# interface_eagle_1.net
KiCad netlist of a schematic drawn in Altium Designer
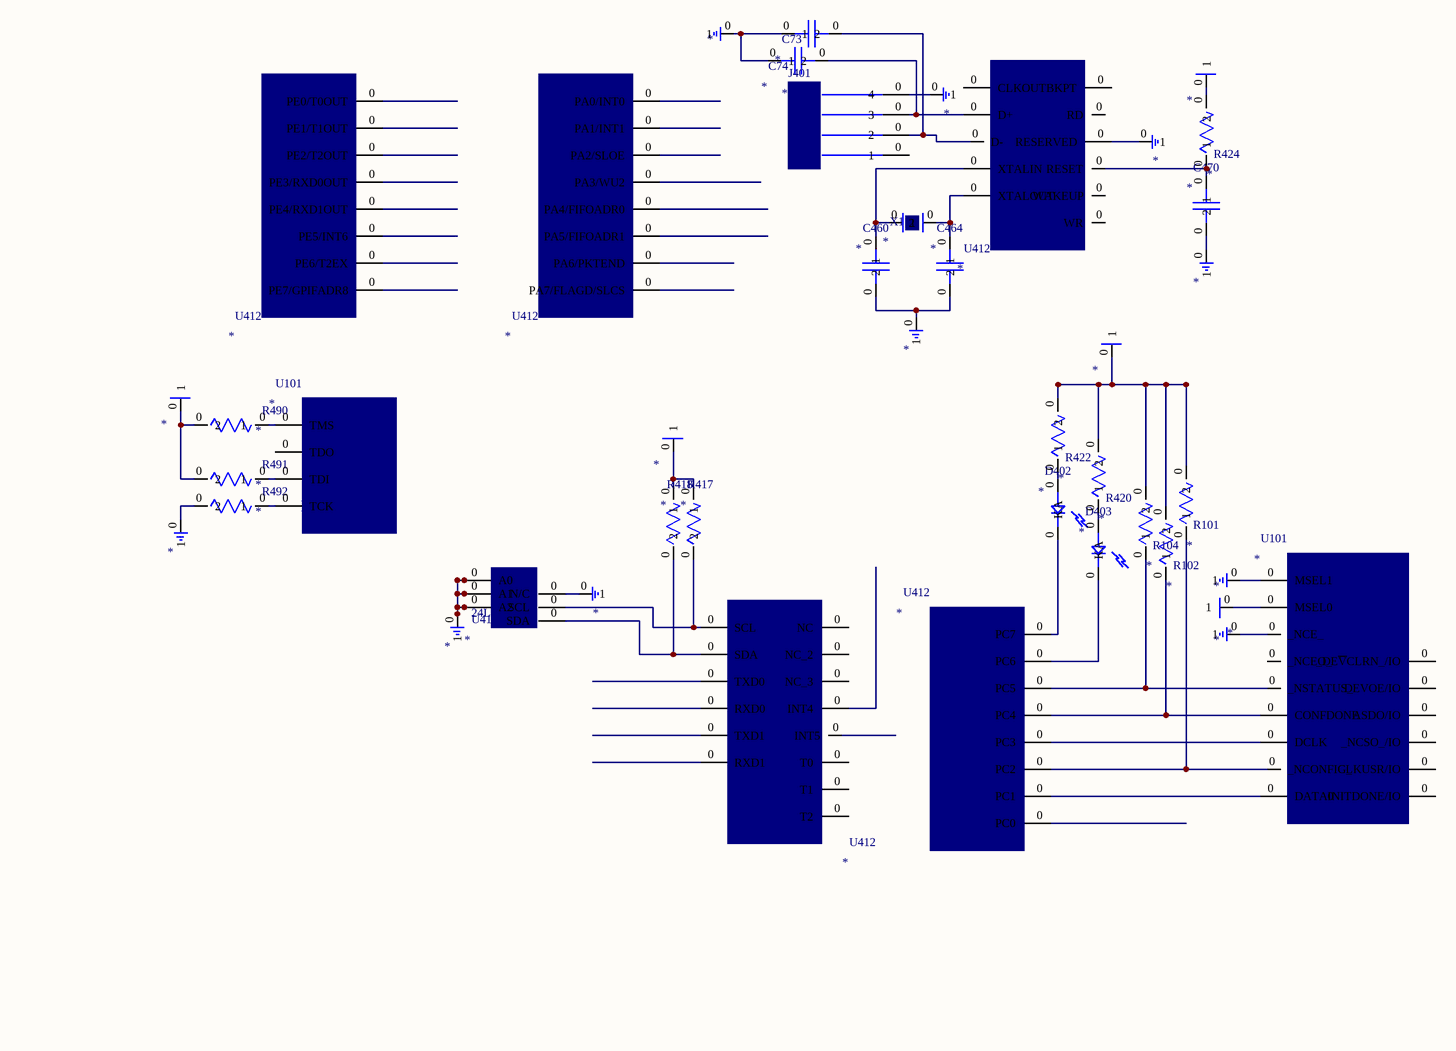
[diagram p0: interface_eagle_1.SchDoc]

(export (version "E")
  (design (tool "Eeschema 10.0.6"))
  (components
    (comp (ref "C73") (value "*") (libsource (lib "") (part "CAPACITOR-1_3")))
    (comp (ref "C74") (value "*") (libsource (lib "") (part "CAPACITOR-1_4")))
    (comp (ref "C460") (value "*") (libsource (lib "") (part "CAPACITOR-1_1")))
    (comp (ref "C464") (value "*") (libsource (lib "") (part "CAPACITOR-1_2")))
    (comp (ref "C470") (value "*") (libsource (lib "openjson") (part "CAPACITOR-1")))
    (comp (ref "D402") (value "*") (libsource (lib "openjson") (part "LED-1")))
    (comp (ref "D403") (value "*") (libsource (lib "") (part "LED-1_1")))
    (comp (ref "GENERIC-POWER") (value "*") (libsource (lib "openjson") (part "GENERIC-POWER")))
    (comp (ref "GENERIC-POWER-4") (value "*") (libsource (lib "openjson") (part "GENERIC-POWER")))
    (comp (ref "GENERIC-POWER-9") (value "*") (libsource (lib "openjson") (part "GENERIC-POWER")))
    (comp (ref "GENERIC-POWER-10") (value "*") (libsource (lib "openjson") (part "GENERIC-POWER")))
    (comp (ref "GENERIC-POWER-14") (value "*") (libsource (lib "openjson") (part "GENERIC-POWER")))
    (comp (ref "GND-1") (value "*") (libsource (lib "openjson") (part "GND-1")))
    (comp (ref "GND-1-3") (value "*") (libsource (lib "openjson") (part "GND-1")))
    (comp (ref "GND-1-5") (value "*") (libsource (lib "") (part "GND-1_1")))
    (comp (ref "GND-1-6") (value "*") (libsource (lib "") (part "GND-1_2")))
    (comp (ref "GND-1-7") (value "*") (libsource (lib "") (part "GND-1_1")))
    (comp (ref "GND-1-8") (value "*") (libsource (lib "") (part "GND-1_2")))
    (comp (ref "GND-1-11") (value "*") (libsource (lib "") (part "GND-1_2")))
    (comp (ref "GND-1-12") (value "*") (libsource (lib "") (part "GND-1_1")))
    (comp (ref "GND-1-13") (value "*") (libsource (lib "") (part "GND-1_2")))
    (comp (ref "GND-1-17") (value "*") (libsource (lib "openjson") (part "GND-1")))
    (comp (ref "J401") (value "*") (libsource (lib "openjson") (part "CONNECTOR4-1_MIRRORED")))
    (comp (ref "R101") (value "*") (libsource (lib "") (part "RESISTOR-1_10")))
    (comp (ref "R102") (value "*") (libsource (lib "") (part "RESISTOR-1_9")))
    (comp (ref "R104") (value "*") (libsource (lib "") (part "RESISTOR-1_1")))
    (comp (ref "R417") (value "*") (libsource (lib "") (part "RESISTOR-1_8")))
    (comp (ref "R418") (value "*") (libsource (lib "") (part "RESISTOR-1_5")))
    (comp (ref "R420") (value "*") (libsource (lib "") (part "RESISTOR-1_3")))
    (comp (ref "R422") (value "*") (libsource (lib "openjson") (part "RESISTOR-1")))
    (comp (ref "R424") (value "*") (libsource (lib "") (part "RESISTOR-1_2")))
    (comp (ref "R490") (value "*") (libsource (lib "") (part "RESISTOR-1_4")))
    (comp (ref "R491") (value "*") (libsource (lib "") (part "RESISTOR-1_7")))
    (comp (ref "R492") (value "*") (libsource (lib "") (part "RESISTOR-1_6")))
    (comp (ref "U101") (value "*") (libsource (lib "openjson") (part "EP1C12-PQ240-CFG_MIRRORED")))
    (comp (ref "U101-2") (value "*") (libsource (lib "openjson") (part "EP1C12-PQ240-JTAG_MIRRORED")))
    (comp (ref "U412") (value "*") (libsource (lib "openjson") (part "CY7C68013-TQ100-CTRL")))
    (comp (ref "U412-0") (value "*") (libsource (lib "openjson") (part "CY7C68013-TQ100-MISC_MIRRORED")))
    (comp (ref "U412-1") (value "*") (libsource (lib "openjson") (part "CY7C68013-TQ100-PC_MIRRORED")))
    (comp (ref "U412-15") (value "*") (libsource (lib "openjson") (part "CY7C68013-TQ100-PA")))
    (comp (ref "U412-16") (value "*") (libsource (lib "openjson") (part "CY7C68013-TQ100-PE")))
    (comp (ref "U413") (value "*") (libsource (lib "openjson") (part "24CXX-1")))
    (comp (ref "X1") (value "*") (libsource (lib "openjson") (part "CRYSTAL-1")))
  )
  (nets
    (net (code "1") (name "Net-(C73-1)") (class "Default")
      (node (ref "C73") (pin "0") (pinfunction "1_0") (pintype "passive"))
      (node (ref "C74") (pin "0") (pinfunction "1_0") (pintype "passive"))
      (node (ref "GND-1-17") (pin "0") (pinfunction "1_0") (pintype "passive"))
    )
    (net (code "2") (name "Net-(C73-2)") (class "Default")
      (node (ref "C73") (pin "0") (pinfunction "2_0") (pintype "passive"))
      (node (ref "J401") (pin "0") (pinfunction "2_0") (pintype "passive"))
      (node (ref "U412") (pin "0") (pinfunction "D-_0") (pintype "passive"))
    )
    (net (code "3") (name "Net-(C74-2)") (class "Default")
      (node (ref "C74") (pin "0") (pinfunction "2_0") (pintype "passive"))
      (node (ref "J401") (pin "0") (pinfunction "3_0") (pintype "passive"))
      (node (ref "U412") (pin "0") (pinfunction "D+_0") (pintype "passive"))
    )
    (net (code "4") (name "Net-(C460-1)") (class "Default")
      (node (ref "C460") (pin "0") (pinfunction "1_0") (pintype "passive"))
      (node (ref "U412") (pin "0") (pinfunction "XTALIN_0") (pintype "passive"))
      (node (ref "X1") (pin "0") (pinfunction "1_0") (pintype "passive"))
    )
    (net (code "5") (name "Net-(C460-2)") (class "Default")
      (node (ref "C460") (pin "0") (pinfunction "2_0") (pintype "passive"))
      (node (ref "C464") (pin "0") (pinfunction "2_0") (pintype "passive"))
      (node (ref "GND-1-6") (pin "0") (pinfunction "1_0") (pintype "passive"))
    )
    (net (code "6") (name "Net-(C464-1)") (class "Default")
      (node (ref "C464") (pin "0") (pinfunction "1_0") (pintype "passive"))
      (node (ref "U412") (pin "0") (pinfunction "XTALOUT_0") (pintype "passive"))
      (node (ref "X1") (pin "0") (pinfunction "2_0") (pintype "passive"))
    )
    (net (code "7") (name "Net-(C470-1)") (class "Default")
      (node (ref "C470") (pin "0") (pinfunction "1_0") (pintype "passive"))
      (node (ref "R424") (pin "0") (pinfunction "1_0") (pintype "passive"))
      (node (ref "U412") (pin "0") (pinfunction "RESET_0") (pintype "passive"))
    )
    (net (code "8") (name "Net-(C470-2)") (class "Default")
      (node (ref "C470") (pin "0") (pinfunction "2_0") (pintype "passive"))
      (node (ref "GND-1-8") (pin "0") (pinfunction "1_0") (pintype "passive"))
    )
    (net (code "9") (name "Net-(D402-A)") (class "Default")
      (node (ref "D402") (pin "0") (pinfunction "A_0") (pintype "passive"))
      (node (ref "R422") (pin "0") (pinfunction "1_0") (pintype "passive"))
    )
    (net (code "10") (name "Net-(D402-K)") (class "Default")
      (node (ref "D402") (pin "0") (pinfunction "K_0") (pintype "passive"))
      (node (ref "U412-1") (pin "0") (pinfunction "PC7_0") (pintype "passive"))
    )
    (net (code "11") (name "Net-(D403-A)") (class "Default")
      (node (ref "D403") (pin "0") (pinfunction "A_0") (pintype "passive"))
      (node (ref "R420") (pin "0") (pinfunction "1_0") (pintype "passive"))
    )
    (net (code "12") (name "Net-(D403-K)") (class "Default")
      (node (ref "D403") (pin "0") (pinfunction "K_0") (pintype "passive"))
      (node (ref "U412-1") (pin "0") (pinfunction "PC6_0") (pintype "passive"))
    )
    (net (code "13") (name "Net-(GENERIC-POWER-1)") (class "Default")
      (node (ref "GENERIC-POWER") (pin "0") (pinfunction "1_0") (pintype "passive"))
      (node (ref "U101") (pin "0") (pinfunction "MSEL0_0") (pintype "passive"))
    )
    (net (code "14") (name "Net-(GENERIC-POWER-4-1)") (class "Default")
      (node (ref "GENERIC-POWER-4") (pin "0") (pinfunction "1_0") (pintype "passive"))
      (node (ref "R101") (pin "0") (pinfunction "2_0") (pintype "passive"))
      (node (ref "R102") (pin "0") (pinfunction "2_0") (pintype "passive"))
      (node (ref "R104") (pin "0") (pinfunction "2_0") (pintype "passive"))
      (node (ref "R420") (pin "0") (pinfunction "2_0") (pintype "passive"))
      (node (ref "R422") (pin "0") (pinfunction "2_0") (pintype "passive"))
    )
    (net (code "15") (name "Net-(GENERIC-POWER-9-1)") (class "Default")
      (node (ref "GENERIC-POWER-9") (pin "0") (pinfunction "1_0") (pintype "passive"))
      (node (ref "R424") (pin "0") (pinfunction "2_0") (pintype "passive"))
    )
    (net (code "16") (name "Net-(GENERIC-POWER-10-1)") (class "Default")
      (node (ref "GENERIC-POWER-10") (pin "0") (pinfunction "1_0") (pintype "passive"))
      (node (ref "R490") (pin "0") (pinfunction "2_0") (pintype "passive"))
      (node (ref "R491") (pin "0") (pinfunction "2_0") (pintype "passive"))
    )
    (net (code "17") (name "Net-(GENERIC-POWER-14-1)") (class "Default")
      (node (ref "GENERIC-POWER-14") (pin "0") (pinfunction "1_0") (pintype "passive"))
      (node (ref "R417") (pin "0") (pinfunction "1_0") (pintype "passive"))
      (node (ref "R418") (pin "0") (pinfunction "1_0") (pintype "passive"))
    )
    (net (code "18") (name "Net-(GND-1-1)") (class "Default")
      (node (ref "GND-1") (pin "0") (pinfunction "1_0") (pintype "passive"))
      (node (ref "U101") (pin "0") (pinfunction "_NCE__0") (pintype "passive"))
    )
    (net (code "19") (name "Net-(GND-1-3-1)") (class "Default")
      (node (ref "GND-1-3") (pin "0") (pinfunction "1_0") (pintype "passive"))
      (node (ref "U101") (pin "0") (pinfunction "MSEL1_0") (pintype "passive"))
    )
    (net (code "20") (name "Net-(GND-1-5-1)") (class "Default")
      (node (ref "GND-1-5") (pin "0") (pinfunction "1_0") (pintype "passive"))
      (node (ref "J401") (pin "0") (pinfunction "4_0") (pintype "passive"))
    )
    (net (code "21") (name "Net-(GND-1-7-1)") (class "Default")
      (node (ref "GND-1-7") (pin "0") (pinfunction "1_0") (pintype "passive"))
      (node (ref "U412") (pin "0") (pinfunction "RESERVED_0") (pintype "passive"))
    )
    (net (code "22") (name "Net-(GND-1-11-1)") (class "Default")
      (node (ref "GND-1-11") (pin "0") (pinfunction "1_0") (pintype "passive"))
      (node (ref "R492") (pin "0") (pinfunction "2_0") (pintype "passive"))
    )
    (net (code "23") (name "Net-(GND-1-12-1)") (class "Default")
      (node (ref "GND-1-12") (pin "0") (pinfunction "1_0") (pintype "passive"))
      (node (ref "U413") (pin "0") (pinfunction "N/C_0") (pintype "passive"))
    )
    (net (code "24") (name "Net-(GND-1-13-1)") (class "Default")
      (node (ref "GND-1-13") (pin "0") (pinfunction "1_0") (pintype "passive"))
      (node (ref "U413") (pin "0") (pinfunction "A0_0") (pintype "passive"))
    )
    (net (code "25") (name "Net-(R101-1)") (class "Default")
      (node (ref "R101") (pin "0") (pinfunction "1_0") (pintype "passive"))
      (node (ref "U101") (pin "0") (pinfunction "_NCONFIG__0") (pintype "passive"))
      (node (ref "U412-1") (pin "0") (pinfunction "PC2_0") (pintype "passive"))
    )
    (net (code "26") (name "Net-(R102-1)") (class "Default")
      (node (ref "R102") (pin "0") (pinfunction "1_0") (pintype "passive"))
      (node (ref "U101") (pin "0") (pinfunction "CONFDONE_0") (pintype "passive"))
      (node (ref "U412-1") (pin "0") (pinfunction "PC4_0") (pintype "passive"))
    )
    (net (code "27") (name "Net-(R104-1)") (class "Default")
      (node (ref "R104") (pin "0") (pinfunction "1_0") (pintype "passive"))
      (node (ref "U101") (pin "0") (pinfunction "_NSTATUS__0") (pintype "passive"))
      (node (ref "U412-1") (pin "0") (pinfunction "PC5_0") (pintype "passive"))
    )
    (net (code "28") (name "Net-(R417-2)") (class "Default")
      (node (ref "R417") (pin "0") (pinfunction "2_0") (pintype "passive"))
      (node (ref "U412-0") (pin "0") (pinfunction "SCL_0") (pintype "passive"))
      (node (ref "U413") (pin "0") (pinfunction "SCL_0") (pintype "passive"))
    )
    (net (code "29") (name "Net-(R418-2)") (class "Default")
      (node (ref "R418") (pin "0") (pinfunction "2_0") (pintype "passive"))
      (node (ref "U412-0") (pin "0") (pinfunction "SDA_0") (pintype "passive"))
      (node (ref "U413") (pin "0") (pinfunction "SDA_0") (pintype "passive"))
    )
    (net (code "30") (name "Net-(R490-1)") (class "Default")
      (node (ref "R490") (pin "0") (pinfunction "1_0") (pintype "passive"))
      (node (ref "U101-2") (pin "0") (pinfunction "TMS_0") (pintype "passive"))
    )
    (net (code "31") (name "Net-(R491-1)") (class "Default")
      (node (ref "R491") (pin "0") (pinfunction "1_0") (pintype "passive"))
      (node (ref "U101-2") (pin "0") (pinfunction "TDI_0") (pintype "passive"))
    )
    (net (code "32") (name "Net-(R492-1)") (class "Default")
      (node (ref "R492") (pin "0") (pinfunction "1_0") (pintype "passive"))
      (node (ref "U101-2") (pin "0") (pinfunction "TCK_0") (pintype "passive"))
    )
    (net (code "33") (name "Net-(U101-DATA0)") (class "Default")
      (node (ref "U101") (pin "0") (pinfunction "DATA0_0") (pintype "passive"))
      (node (ref "U412-1") (pin "0") (pinfunction "PC1_0") (pintype "passive"))
    )
    (net (code "34") (name "Net-(U101-DCLK)") (class "Default")
      (node (ref "U101") (pin "0") (pinfunction "DCLK_0") (pintype "passive"))
      (node (ref "U412-1") (pin "0") (pinfunction "PC3_0") (pintype "passive"))
    )
    (net (code "35") (name "unconnected-(J401-1-Pad0)") (class "Default")
      (node (ref "J401") (pin "0") (pinfunction "1_0") (pintype "passive"))
    )
    (net (code "36") (name "unconnected-(U101-2-TDO-Pad0)") (class "Default")
      (node (ref "U101-2") (pin "0") (pinfunction "TDO_0") (pintype "passive"))
    )
    (net (code "37") (name "unconnected-(U101-ASDO{slash}IO-Pad0)") (class "Default")
      (node (ref "U101") (pin "0") (pinfunction "ASDO/IO_0") (pintype "passive"))
    )
    (net (code "38") (name "unconnected-(U101-CLKUSR{slash}IO-Pad0)") (class "Default")
      (node (ref "U101") (pin "0") (pinfunction "CLKUSR/IO_0") (pintype "passive"))
    )
    (net (code "39") (name "unconnected-(U101-DEVOE{slash}IO-Pad0)") (class "Default")
      (node (ref "U101") (pin "0") (pinfunction "DEVOE/IO_0") (pintype "passive"))
    )
    (net (code "40") (name "unconnected-(U101-INITDONE{slash}IO-Pad0)") (class "Default")
      (node (ref "U101") (pin "0") (pinfunction "INITDONE/IO_0") (pintype "passive"))
    )
    (net (code "41") (name "unconnected-(U101-_DE~{V}CLRN_{slash}IO-Pad0)") (class "Default")
      (node (ref "U101") (pin "0") (pinfunction "_DE~{V}CLRN_/IO_0") (pintype "passive"))
    )
    (net (code "42") (name "unconnected-(U101-_NCEO_-Pad0)") (class "Default")
      (node (ref "U101") (pin "0") (pinfunction "_NCEO__0") (pintype "passive"))
    )
    (net (code "43") (name "unconnected-(U101-_NCSO_{slash}IO-Pad0)") (class "Default")
      (node (ref "U101") (pin "0") (pinfunction "_NCSO_/IO_0") (pintype "passive"))
    )
    (net (code "44") (name "unconnected-(U412-0-INT4-Pad0)") (class "Default")
      (node (ref "U412-0") (pin "0") (pinfunction "INT4_0") (pintype "passive"))
    )
    (net (code "45") (name "unconnected-(U412-0-INT5-Pad0)") (class "Default")
      (node (ref "U412-0") (pin "0") (pinfunction "INT5_0") (pintype "passive"))
    )
    (net (code "46") (name "unconnected-(U412-0-NC-Pad0)") (class "Default")
      (node (ref "U412-0") (pin "0") (pinfunction "NC_0") (pintype "passive"))
    )
    (net (code "47") (name "unconnected-(U412-0-NC_2-Pad0)") (class "Default")
      (node (ref "U412-0") (pin "0") (pinfunction "NC_2_0") (pintype "passive"))
    )
    (net (code "48") (name "unconnected-(U412-0-NC_3-Pad0)") (class "Default")
      (node (ref "U412-0") (pin "0") (pinfunction "NC_3_0") (pintype "passive"))
    )
    (net (code "49") (name "unconnected-(U412-0-RXD0-Pad0)") (class "Default")
      (node (ref "U412-0") (pin "0") (pinfunction "RXD0_0") (pintype "passive"))
    )
    (net (code "50") (name "unconnected-(U412-0-RXD1-Pad0)") (class "Default")
      (node (ref "U412-0") (pin "0") (pinfunction "RXD1_0") (pintype "passive"))
    )
    (net (code "51") (name "unconnected-(U412-0-T0-Pad0)") (class "Default")
      (node (ref "U412-0") (pin "0") (pinfunction "T0_0") (pintype "passive"))
    )
    (net (code "52") (name "unconnected-(U412-0-T1-Pad0)") (class "Default")
      (node (ref "U412-0") (pin "0") (pinfunction "T1_0") (pintype "passive"))
    )
    (net (code "53") (name "unconnected-(U412-0-T2-Pad0)") (class "Default")
      (node (ref "U412-0") (pin "0") (pinfunction "T2_0") (pintype "passive"))
    )
    (net (code "54") (name "unconnected-(U412-0-TXD0-Pad0)") (class "Default")
      (node (ref "U412-0") (pin "0") (pinfunction "TXD0_0") (pintype "passive"))
    )
    (net (code "55") (name "unconnected-(U412-0-TXD1-Pad0)") (class "Default")
      (node (ref "U412-0") (pin "0") (pinfunction "TXD1_0") (pintype "passive"))
    )
    (net (code "56") (name "unconnected-(U412-1-PC0-Pad0)") (class "Default")
      (node (ref "U412-1") (pin "0") (pinfunction "PC0_0") (pintype "passive"))
    )
    (net (code "57") (name "unconnected-(U412-15-PA0{slash}INT0-Pad0)") (class "Default")
      (node (ref "U412-15") (pin "0") (pinfunction "PA0/INT0_0") (pintype "passive"))
    )
    (net (code "58") (name "unconnected-(U412-15-PA1{slash}INT1-Pad0)") (class "Default")
      (node (ref "U412-15") (pin "0") (pinfunction "PA1/INT1_0") (pintype "passive"))
    )
    (net (code "59") (name "unconnected-(U412-15-PA2{slash}SLOE-Pad0)") (class "Default")
      (node (ref "U412-15") (pin "0") (pinfunction "PA2/SLOE_0") (pintype "passive"))
    )
    (net (code "60") (name "unconnected-(U412-15-PA3{slash}WU2-Pad0)") (class "Default")
      (node (ref "U412-15") (pin "0") (pinfunction "PA3/WU2_0") (pintype "passive"))
    )
    (net (code "61") (name "unconnected-(U412-15-PA4{slash}FIFOADR0-Pad0)") (class "Default")
      (node (ref "U412-15") (pin "0") (pinfunction "PA4/FIFOADR0_0") (pintype "passive"))
    )
    (net (code "62") (name "unconnected-(U412-15-PA5{slash}FIFOADR1-Pad0)") (class "Default")
      (node (ref "U412-15") (pin "0") (pinfunction "PA5/FIFOADR1_0") (pintype "passive"))
    )
    (net (code "63") (name "unconnected-(U412-15-PA6{slash}PKTEND-Pad0)") (class "Default")
      (node (ref "U412-15") (pin "0") (pinfunction "PA6/PKTEND_0") (pintype "passive"))
    )
    (net (code "64") (name "unconnected-(U412-15-PA7{slash}FLAGD{slash}SLCS-Pad0)") (class "Default")
      (node (ref "U412-15") (pin "0") (pinfunction "PA7/FLAGD/SLCS_0") (pintype "passive"))
    )
    (net (code "65") (name "unconnected-(U412-16-PE0{slash}T0OUT-Pad0)") (class "Default")
      (node (ref "U412-16") (pin "0") (pinfunction "PE0/T0OUT_0") (pintype "passive"))
    )
    (net (code "66") (name "unconnected-(U412-16-PE1{slash}T1OUT-Pad0)") (class "Default")
      (node (ref "U412-16") (pin "0") (pinfunction "PE1/T1OUT_0") (pintype "passive"))
    )
    (net (code "67") (name "unconnected-(U412-16-PE2{slash}T2OUT-Pad0)") (class "Default")
      (node (ref "U412-16") (pin "0") (pinfunction "PE2/T2OUT_0") (pintype "passive"))
    )
    (net (code "68") (name "unconnected-(U412-16-PE3{slash}RXD0OUT-Pad0)") (class "Default")
      (node (ref "U412-16") (pin "0") (pinfunction "PE3/RXD0OUT_0") (pintype "passive"))
    )
    (net (code "69") (name "unconnected-(U412-16-PE4{slash}RXD1OUT-Pad0)") (class "Default")
      (node (ref "U412-16") (pin "0") (pinfunction "PE4/RXD1OUT_0") (pintype "passive"))
    )
    (net (code "70") (name "unconnected-(U412-16-PE5{slash}INT6-Pad0)") (class "Default")
      (node (ref "U412-16") (pin "0") (pinfunction "PE5/INT6_0") (pintype "passive"))
    )
    (net (code "71") (name "unconnected-(U412-16-PE6{slash}T2EX-Pad0)") (class "Default")
      (node (ref "U412-16") (pin "0") (pinfunction "PE6/T2EX_0") (pintype "passive"))
    )
    (net (code "72") (name "unconnected-(U412-16-PE7{slash}GPIFADR8-Pad0)") (class "Default")
      (node (ref "U412-16") (pin "0") (pinfunction "PE7/GPIFADR8_0") (pintype "passive"))
    )
    (net (code "73") (name "unconnected-(U412-BKPT-Pad0)") (class "Default")
      (node (ref "U412") (pin "0") (pinfunction "BKPT_0") (pintype "passive"))
    )
    (net (code "74") (name "unconnected-(U412-CLKOUT-Pad0)") (class "Default")
      (node (ref "U412") (pin "0") (pinfunction "CLKOUT_0") (pintype "passive"))
    )
    (net (code "75") (name "unconnected-(U412-RD-Pad0)") (class "Default")
      (node (ref "U412") (pin "0") (pinfunction "RD_0") (pintype "passive"))
    )
    (net (code "76") (name "unconnected-(U412-WAKEUP-Pad0)") (class "Default")
      (node (ref "U412") (pin "0") (pinfunction "WAKEUP_0") (pintype "passive"))
    )
    (net (code "77") (name "unconnected-(U412-WR-Pad0)") (class "Default")
      (node (ref "U412") (pin "0") (pinfunction "WR_0") (pintype "passive"))
    )
  )
)
